# k26_baseboard_fan.net
KiCad netlist of a schematic drawn in Altium Designer
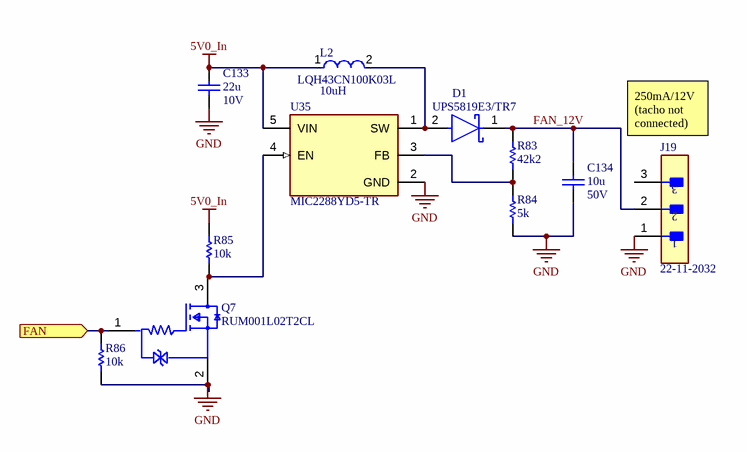
[diagram p0: k26_baseboard_fan.SchDoc]

(export (version "E")
  (design (tool "Eeschema 10.0.6"))
  (components
    (comp (ref "C133")
      (value "22u")
      (footprint "k26_FPGA_drone_baseboard:CAPC1206")
      (fields
        (field (name "MANUFACTURER") "Kyocera AVX")
        (field (name "MANUFACTURER PART NUMBER") "1206ZC226KAT2A")
        (field (name "RATED DC VOLTAGE (URDC)") "10V")
      )
      (libsource (lib "k26_FPGA_drone_baseboard") (part "cap1206"))
    )
    (comp (ref "C134")
      (value "10u")
      (footprint "k26_FPGA_drone_baseboard:CAPC1206")
      (fields
        (field (name "MANUFACTURER") "Murata")
        (field (name "MANUFACTURER PART NUMBER") "GRM31CR61H106KA12L")
        (field (name "RATED DC VOLTAGE (URDC)") "50V")
      )
      (libsource (lib "k26_FPGA_drone_baseboard") (part "cap1206"))
    )
    (comp (ref "D1")
      (value "UPS5819E3/TR7")
      (footprint "FP-457-04-MFG")
      (description "DIODE SCHOTTKY 40V 1A POWERMITE")
      (fields
        (field (name "MANUFACTURER") "ON Semiconductor")
        (field (name "MANUFACTURER PART NUMBER") "MBRM140T3G")
      )
      (libsource (lib "k26_FPGA_drone_baseboard") (part "CMP-1055-00293-2"))
    )
    (comp (ref "J19")
      (value "22-11-2032")
      (footprint "FP-22-11-2032-MFG")
      (description "CONN HEADER VERT 3POS 2.54MM")
      (fields
        (field (name "MANUFACTURER") "Molex")
        (field (name "OCTOPART") "https://octopart.com/22-11-2032-molex-10085")
      )
      (libsource (lib "k26_FPGA_drone_baseboard") (part "CMP-04776-000113-1"))
    )
    (comp (ref "L2")
      (value "LQH43CN100K03L")
      (footprint "FP-LQH43CN_03-MFG")
      (description "FIXED IND 10UH 650MA 240 MOHM")
      (fields
        (field (name "INDUCTANCE") "10uH")
        (field (name "TOLERANCE") "10%")
        (field (name "MANUFACTURER") "Murata")
      )
      (libsource (lib "k26_FPGA_drone_baseboard") (part "CMP-06042-000232-1"))
    )
    (comp (ref "Q7")
      (value "RUM001L02T2CL")
      (footprint "FP-VMT3-MFG")
      (description "MOSFET N-CH 20V 0.1A VMT3")
      (fields
        (field (name "MANUFACTURER") "Rohm")
        (field (name "OCTOPART") "https://octopart.com/rum001l02t2cl-rohm-24403092")
      )
      (libsource (lib "k26_FPGA_drone_baseboard") (part "CMP-08982-000008-1"))
    )
    (comp (ref "R83")
      (value "42k2")
      (footprint "k26_FPGA_drone_baseboard:RES0402")
      (fields
        (field (name "MANUFACTURER") "Vishay")
        (field (name "MANUFACTURER PART NUMBER") "CRCW040242K2FKED")
        (field (name "TOLERANCE") "1%")
      )
      (libsource (lib "k26_FPGA_drone_baseboard") (part "res0402"))
    )
    (comp (ref "R84")
      (value "5k")
      (footprint "k26_FPGA_drone_baseboard:RES0402")
      (description "Fixed Resistor, Thin Film, 0.05W, 5000ohm, 75V, 0.1% +/-Tol, 25ppm/Cel, Surface Mount, 0402")
      (fields
        (field (name "MANUFACTURER") "Vishay Dale")
        (field (name "MANUFACTURER PART NUMBER") "PNM0402E5001BST1")
      )
      (libsource (lib "k26_FPGA_drone_baseboard") (part "res0402"))
    )
    (comp (ref "R85")
      (value "10k")
      (footprint "k26_FPGA_drone_baseboard:RES0402")
      (fields
        (field (name "MANUFACTURER") "Panasonic")
        (field (name "MANUFACTURER PART NUMBER") "ERJ-2RKF1002X")
        (field (name "TOLERANCE") "1%")
      )
      (libsource (lib "k26_FPGA_drone_baseboard") (part "res0402"))
    )
    (comp (ref "R86")
      (value "10k")
      (footprint "k26_FPGA_drone_baseboard:RES0402")
      (fields
        (field (name "MANUFACTURER") "Panasonic")
        (field (name "MANUFACTURER PART NUMBER") "ERJ-2RKF1002X")
        (field (name "TOLERANCE") "1%")
      )
      (libsource (lib "k26_FPGA_drone_baseboard") (part "res0402"))
    )
    (comp (ref "U35")
      (value "MIC2288YD5-TR")
      (footprint "FP-TSOT-5LD-PL-1-MFG")
      (description "IC REG BOOST ADJ 1.2A TSOT23-5")
      (fields (field (name "MANUFACTURER") "Microchip"))
      (libsource (lib "k26_FPGA_drone_baseboard") (part "CMP-06325-000011-1"))
    )
  )
  (nets
    (net (code "1") (name "/FAN") (class "Default")
      (node (ref "Q7") (pin "1") (pinfunction "Gate_1") (pintype "passive"))
      (node (ref "R86") (pin "2") (pinfunction "2_2") (pintype "passive"))
    )
    (net (code "2") (name "/FAN_12V") (class "Default")
      (node (ref "C134") (pin "2") (pinfunction "2_2") (pintype "passive"))
      (node (ref "D1") (pin "1") (pinfunction "C_1") (pintype "passive"))
      (node (ref "J19") (pin "2") (pinfunction "2_2") (pintype "passive"))
      (node (ref "R83") (pin "2") (pinfunction "2_2") (pintype "passive"))
    )
    (net (code "3") (name "5V0_In") (class "Default")
      (node (ref "C133") (pin "2") (pinfunction "2_2") (pintype "passive"))
      (node (ref "L2") (pin "1") (pinfunction "1_1") (pintype "passive"))
      (node (ref "R85") (pin "2") (pinfunction "2_2") (pintype "passive"))
      (node (ref "U35") (pin "5") (pinfunction "VIN_5") (pintype "power_in"))
    )
    (net (code "4") (name "GND") (class "Default")
      (node (ref "C133") (pin "1") (pinfunction "1_1") (pintype "passive"))
      (node (ref "C134") (pin "1") (pinfunction "1_1") (pintype "passive"))
      (node (ref "J19") (pin "1") (pinfunction "1_1") (pintype "passive"))
      (node (ref "Q7") (pin "2") (pinfunction "Source_2") (pintype "passive"))
      (node (ref "R84") (pin "1") (pinfunction "1_1") (pintype "passive"))
      (node (ref "R86") (pin "1") (pinfunction "1_1") (pintype "passive"))
      (node (ref "U35") (pin "2") (pinfunction "GND_2") (pintype "power_in"))
    )
    (net (code "5") (name "Net-(D1-A)") (class "Default")
      (node (ref "D1") (pin "2") (pinfunction "A_2") (pintype "passive"))
      (node (ref "L2") (pin "2") (pinfunction "2_2") (pintype "passive"))
      (node (ref "U35") (pin "1") (pinfunction "SW_1") (pintype "power_in"))
    )
    (net (code "6") (name "Net-(Q7-Drain)") (class "Default")
      (node (ref "Q7") (pin "3") (pinfunction "Drain_3") (pintype "passive"))
      (node (ref "R85") (pin "1") (pinfunction "1_1") (pintype "passive"))
      (node (ref "U35") (pin "4") (pinfunction "EN_4") (pintype "input"))
    )
    (net (code "7") (name "Net-(U35-FB)") (class "Default")
      (node (ref "R83") (pin "1") (pinfunction "1_1") (pintype "passive"))
      (node (ref "R84") (pin "2") (pinfunction "2_2") (pintype "passive"))
      (node (ref "U35") (pin "3") (pinfunction "FB_3") (pintype "passive"))
    )
    (net (code "8") (name "unconnected-(J19-Pad3)") (class "Default")
      (node (ref "J19") (pin "3") (pinfunction "3_3") (pintype "passive"))
    )
  )
)
